# spear.net
KiCad netlist of a schematic drawn in EAGLE
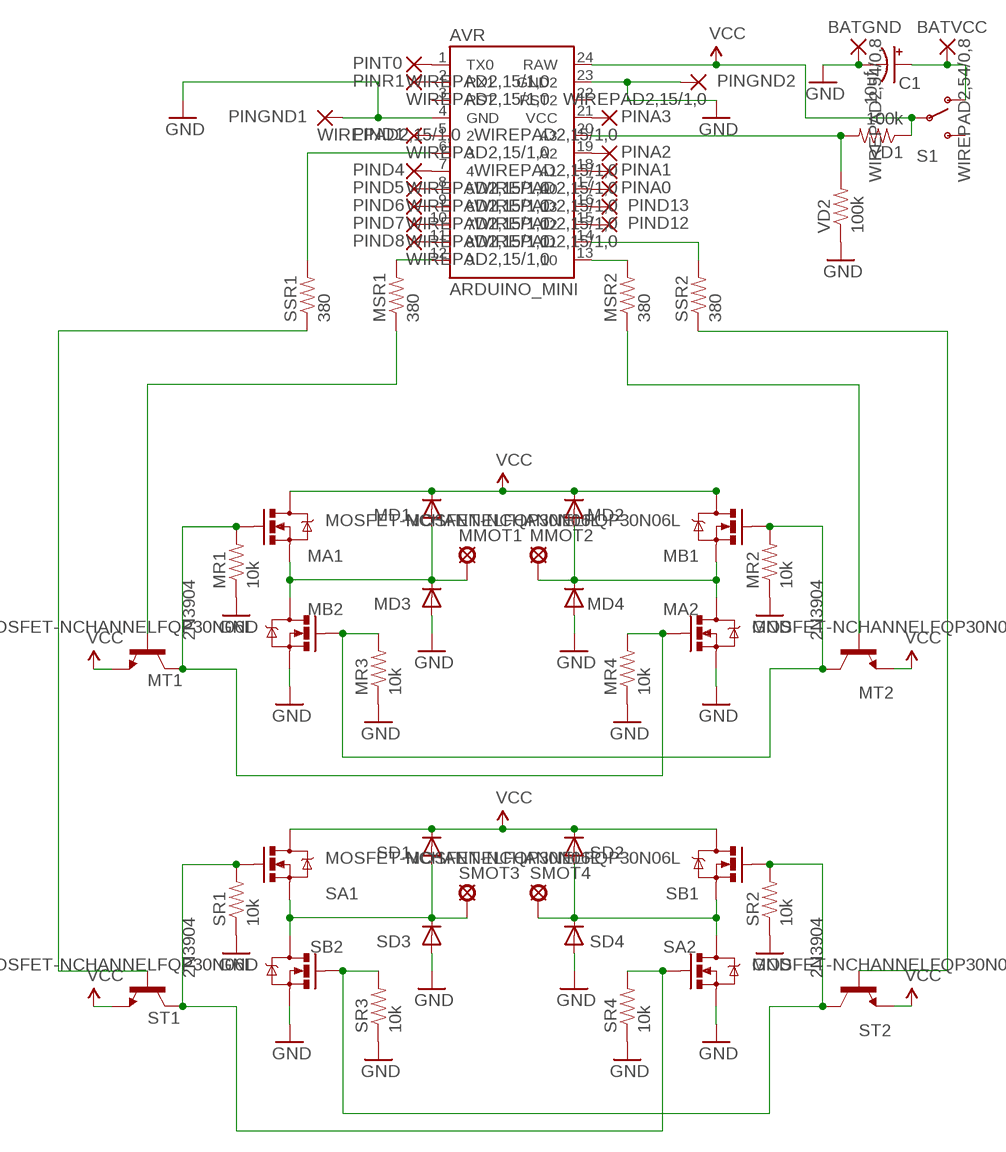
[diagram p0: schematic, sheet 1]

(export (version "E")
  (design (tool "Eeschema 10.0.6"))
  (components
    (comp (ref "AVR")
      (value "ARDUINO_MINI")
      (footprint "eagle-import:ARDUINO_MINI")
      (libsource (lib "eagle-import") (part "ARDUINO_MINI"))
    )
    (comp (ref "BATGND")
      (value "WIREPAD2,54/0,8")
      (footprint "eagle-import:2,54_0,8")
      (libsource (lib "eagle-import") (part "WIREPAD2,54/0,8"))
    )
    (comp (ref "BATVCC")
      (value "WIREPAD2,54/0,8")
      (footprint "eagle-import:2,54_0,8")
      (libsource (lib "eagle-import") (part "WIREPAD2,54/0,8"))
    )
    (comp (ref "C1")
      (value "10uf")
      (footprint "eagle-import:CPOL-RADIAL-10UF-25V")
      (libsource (lib "eagle-import") (part "CAP_POLPTH2"))
    )
    (comp (ref "MA1")
      (value "MOSFET-NCHANNELFQP30N06L")
      (footprint "eagle-import:TO220V")
      (libsource (lib "eagle-import") (part "MOSFET-NCHANNELFQP30N06L"))
    )
    (comp (ref "MA2")
      (value "MOSFET-NCHANNELFQP30N06L")
      (footprint "eagle-import:TO220V")
      (libsource (lib "eagle-import") (part "MOSFET-NCHANNELFQP30N06L"))
    )
    (comp (ref "MB1")
      (value "MOSFET-NCHANNELFQP30N06L")
      (footprint "eagle-import:TO220V")
      (libsource (lib "eagle-import") (part "MOSFET-NCHANNELFQP30N06L"))
    )
    (comp (ref "MB2")
      (value "MOSFET-NCHANNELFQP30N06L")
      (footprint "eagle-import:TO220V")
      (libsource (lib "eagle-import") (part "MOSFET-NCHANNELFQP30N06L"))
    )
    (comp (ref "MD1")
      (value "DIODEPTH")
      (footprint "eagle-import:DIODE-1N4001")
      (libsource (lib "eagle-import") (part "DIODEPTH"))
    )
    (comp (ref "MD2")
      (value "DIODEPTH")
      (footprint "eagle-import:DIODE-1N4001")
      (libsource (lib "eagle-import") (part "DIODEPTH"))
    )
    (comp (ref "MD3")
      (value "DIODEPTH")
      (footprint "eagle-import:DIODE-1N4001")
      (libsource (lib "eagle-import") (part "DIODEPTH"))
    )
    (comp (ref "MD4")
      (value "DIODEPTH")
      (footprint "eagle-import:DIODE-1N4001")
      (libsource (lib "eagle-import") (part "DIODEPTH"))
    )
    (comp (ref "MMOT1")
      (value "LSP13")
      (footprint "eagle-import:LSP13")
      (libsource (lib "eagle-import") (part "LSP13"))
    )
    (comp (ref "MMOT2")
      (value "LSP13")
      (footprint "eagle-import:LSP13")
      (libsource (lib "eagle-import") (part "LSP13"))
    )
    (comp (ref "MR1")
      (value "10k")
      (footprint "eagle-import:AXIAL-0.4")
      (libsource (lib "eagle-import") (part "RESISTORPTH-1/4W"))
    )
    (comp (ref "MR2")
      (value "10k")
      (footprint "eagle-import:AXIAL-0.4")
      (libsource (lib "eagle-import") (part "RESISTORPTH-1/4W"))
    )
    (comp (ref "MR3")
      (value "10k")
      (footprint "eagle-import:AXIAL-0.4")
      (libsource (lib "eagle-import") (part "RESISTORPTH-1/4W"))
    )
    (comp (ref "MR4")
      (value "10k")
      (footprint "eagle-import:AXIAL-0.4")
      (libsource (lib "eagle-import") (part "RESISTORPTH-1/4W"))
    )
    (comp (ref "MSR1")
      (value "380")
      (footprint "eagle-import:AXIAL-0.4")
      (libsource (lib "eagle-import") (part "RESISTORPTH-1/4W"))
    )
    (comp (ref "MSR2")
      (value "380")
      (footprint "eagle-import:AXIAL-0.4")
      (libsource (lib "eagle-import") (part "RESISTORPTH-1/4W"))
    )
    (comp (ref "MT1")
      (value "2N3904")
      (footprint "eagle-import:TO92")
      (libsource (lib "eagle-import") (part "2N3904"))
    )
    (comp (ref "MT2")
      (value "2N3904")
      (footprint "eagle-import:TO92")
      (libsource (lib "eagle-import") (part "2N3904"))
    )
    (comp (ref "PINA0")
      (value "WIREPAD2,15/1,0")
      (footprint "eagle-import:2,15_1,0")
      (libsource (lib "eagle-import") (part "WIREPAD2,15/1,0"))
    )
    (comp (ref "PINA1")
      (value "WIREPAD2,15/1,0")
      (footprint "eagle-import:2,15_1,0")
      (libsource (lib "eagle-import") (part "WIREPAD2,15/1,0"))
    )
    (comp (ref "PINA2")
      (value "WIREPAD2,15/1,0")
      (footprint "eagle-import:2,15_1,0")
      (libsource (lib "eagle-import") (part "WIREPAD2,15/1,0"))
    )
    (comp (ref "PINA3")
      (value "WIREPAD2,15/1,0")
      (footprint "eagle-import:2,15_1,0")
      (libsource (lib "eagle-import") (part "WIREPAD2,15/1,0"))
    )
    (comp (ref "PIND1")
      (value "WIREPAD2,15/1,0")
      (footprint "eagle-import:2,15_1,0")
      (libsource (lib "eagle-import") (part "WIREPAD2,15/1,0"))
    )
    (comp (ref "PIND4")
      (value "WIREPAD2,15/1,0")
      (footprint "eagle-import:2,15_1,0")
      (libsource (lib "eagle-import") (part "WIREPAD2,15/1,0"))
    )
    (comp (ref "PIND5")
      (value "WIREPAD2,15/1,0")
      (footprint "eagle-import:2,15_1,0")
      (libsource (lib "eagle-import") (part "WIREPAD2,15/1,0"))
    )
    (comp (ref "PIND6")
      (value "WIREPAD2,15/1,0")
      (footprint "eagle-import:2,15_1,0")
      (libsource (lib "eagle-import") (part "WIREPAD2,15/1,0"))
    )
    (comp (ref "PIND7")
      (value "WIREPAD2,15/1,0")
      (footprint "eagle-import:2,15_1,0")
      (libsource (lib "eagle-import") (part "WIREPAD2,15/1,0"))
    )
    (comp (ref "PIND8")
      (value "WIREPAD2,15/1,0")
      (footprint "eagle-import:2,15_1,0")
      (libsource (lib "eagle-import") (part "WIREPAD2,15/1,0"))
    )
    (comp (ref "PIND12")
      (value "WIREPAD2,15/1,0")
      (footprint "eagle-import:2,15_1,0")
      (libsource (lib "eagle-import") (part "WIREPAD2,15/1,0"))
    )
    (comp (ref "PIND13")
      (value "WIREPAD2,15/1,0")
      (footprint "eagle-import:2,15_1,0")
      (libsource (lib "eagle-import") (part "WIREPAD2,15/1,0"))
    )
    (comp (ref "PINGND1")
      (value "WIREPAD2,15/1,0")
      (footprint "eagle-import:2,15_1,0")
      (libsource (lib "eagle-import") (part "WIREPAD2,15/1,0"))
    )
    (comp (ref "PINGND2")
      (value "WIREPAD2,15/1,0")
      (footprint "eagle-import:2,15_1,0")
      (libsource (lib "eagle-import") (part "WIREPAD2,15/1,0"))
    )
    (comp (ref "PINR1")
      (value "WIREPAD2,15/1,0")
      (footprint "eagle-import:2,15_1,0")
      (libsource (lib "eagle-import") (part "WIREPAD2,15/1,0"))
    )
    (comp (ref "PINT0")
      (value "WIREPAD2,15/1,0")
      (footprint "eagle-import:2,15_1,0")
      (libsource (lib "eagle-import") (part "WIREPAD2,15/1,0"))
    )
    (comp (ref "S1")
      (value "SWITCH-SPSTPTH")
      (footprint "eagle-import:SWITCH-SPDT")
      (libsource (lib "eagle-import") (part "SWITCH-SPSTPTH"))
    )
    (comp (ref "SA1")
      (value "MOSFET-NCHANNELFQP30N06L")
      (footprint "eagle-import:TO220V")
      (libsource (lib "eagle-import") (part "MOSFET-NCHANNELFQP30N06L"))
    )
    (comp (ref "SA2")
      (value "MOSFET-NCHANNELFQP30N06L")
      (footprint "eagle-import:TO220V")
      (libsource (lib "eagle-import") (part "MOSFET-NCHANNELFQP30N06L"))
    )
    (comp (ref "SB1")
      (value "MOSFET-NCHANNELFQP30N06L")
      (footprint "eagle-import:TO220V")
      (libsource (lib "eagle-import") (part "MOSFET-NCHANNELFQP30N06L"))
    )
    (comp (ref "SB2")
      (value "MOSFET-NCHANNELFQP30N06L")
      (footprint "eagle-import:TO220V")
      (libsource (lib "eagle-import") (part "MOSFET-NCHANNELFQP30N06L"))
    )
    (comp (ref "SD1")
      (value "DIODEPTH")
      (footprint "eagle-import:DIODE-1N4001")
      (libsource (lib "eagle-import") (part "DIODEPTH"))
    )
    (comp (ref "SD2")
      (value "DIODEPTH")
      (footprint "eagle-import:DIODE-1N4001")
      (libsource (lib "eagle-import") (part "DIODEPTH"))
    )
    (comp (ref "SD3")
      (value "DIODEPTH")
      (footprint "eagle-import:DIODE-1N4001")
      (libsource (lib "eagle-import") (part "DIODEPTH"))
    )
    (comp (ref "SD4")
      (value "DIODEPTH")
      (footprint "eagle-import:DIODE-1N4001")
      (libsource (lib "eagle-import") (part "DIODEPTH"))
    )
    (comp (ref "SMOT3")
      (value "LSP13")
      (footprint "eagle-import:LSP13")
      (libsource (lib "eagle-import") (part "LSP13"))
    )
    (comp (ref "SMOT4")
      (value "LSP13")
      (footprint "eagle-import:LSP13")
      (libsource (lib "eagle-import") (part "LSP13"))
    )
    (comp (ref "SR1")
      (value "10k")
      (footprint "eagle-import:AXIAL-0.4")
      (libsource (lib "eagle-import") (part "RESISTORPTH-1/4W"))
    )
    (comp (ref "SR2")
      (value "10k")
      (footprint "eagle-import:AXIAL-0.4")
      (libsource (lib "eagle-import") (part "RESISTORPTH-1/4W"))
    )
    (comp (ref "SR3")
      (value "10k")
      (footprint "eagle-import:AXIAL-0.4")
      (libsource (lib "eagle-import") (part "RESISTORPTH-1/4W"))
    )
    (comp (ref "SR4")
      (value "10k")
      (footprint "eagle-import:AXIAL-0.4")
      (libsource (lib "eagle-import") (part "RESISTORPTH-1/4W"))
    )
    (comp (ref "SSR1")
      (value "380")
      (footprint "eagle-import:AXIAL-0.4")
      (libsource (lib "eagle-import") (part "RESISTORPTH-1/4W"))
    )
    (comp (ref "SSR2")
      (value "380")
      (footprint "eagle-import:AXIAL-0.4")
      (libsource (lib "eagle-import") (part "RESISTORPTH-1/4W"))
    )
    (comp (ref "ST1")
      (value "2N3904")
      (footprint "eagle-import:TO92")
      (libsource (lib "eagle-import") (part "2N3904"))
    )
    (comp (ref "ST2")
      (value "2N3904")
      (footprint "eagle-import:TO92")
      (libsource (lib "eagle-import") (part "2N3904"))
    )
    (comp (ref "VD1")
      (value "100k")
      (footprint "eagle-import:AXIAL-0.4")
      (libsource (lib "eagle-import") (part "RESISTORPTH-1/4W"))
    )
    (comp (ref "VD2")
      (value "100k")
      (footprint "eagle-import:AXIAL-0.4")
      (libsource (lib "eagle-import") (part "RESISTORPTH-1/4W"))
    )
  )
  (nets
    (net (code "1") (name "GND") (class "Default")
      (node (ref "AVR") (pin "23") (pinfunction "GND2_23") (pintype "bidirectional"))
      (node (ref "AVR") (pin "4") (pinfunction "GND_4") (pintype "bidirectional"))
      (node (ref "BATGND") (pin "1") (pinfunction "P_1") (pintype "passive"))
      (node (ref "C1") (pin "2") (pinfunction "-_2") (pintype "passive"))
      (node (ref "MA2") (pin "3") (pinfunction "S_3") (pintype "passive"))
      (node (ref "MB2") (pin "3") (pinfunction "S_3") (pintype "passive"))
      (node (ref "MD3") (pin "A") (pinfunction "A_A") (pintype "passive"))
      (node (ref "MD4") (pin "A") (pinfunction "A_A") (pintype "passive"))
      (node (ref "MR1") (pin "P$1") (pinfunction "1_P$1") (pintype "passive"))
      (node (ref "MR2") (pin "P$1") (pinfunction "1_P$1") (pintype "passive"))
      (node (ref "MR3") (pin "P$1") (pinfunction "1_P$1") (pintype "passive"))
      (node (ref "MR4") (pin "P$1") (pinfunction "1_P$1") (pintype "passive"))
      (node (ref "PINGND1") (pin "1") (pinfunction "P_1") (pintype "passive"))
      (node (ref "PINGND2") (pin "1") (pinfunction "P_1") (pintype "passive"))
      (node (ref "SA2") (pin "3") (pinfunction "S_3") (pintype "passive"))
      (node (ref "SB2") (pin "3") (pinfunction "S_3") (pintype "passive"))
      (node (ref "SD3") (pin "A") (pinfunction "A_A") (pintype "passive"))
      (node (ref "SD4") (pin "A") (pinfunction "A_A") (pintype "passive"))
      (node (ref "SR1") (pin "P$1") (pinfunction "1_P$1") (pintype "passive"))
      (node (ref "SR2") (pin "P$1") (pinfunction "1_P$1") (pintype "passive"))
      (node (ref "SR3") (pin "P$1") (pinfunction "1_P$1") (pintype "passive"))
      (node (ref "SR4") (pin "P$1") (pinfunction "1_P$1") (pintype "passive"))
      (node (ref "VD2") (pin "P$1") (pinfunction "1_P$1") (pintype "passive"))
    )
    (net (code "2") (name "Net-(AVR-2)") (class "Default")
      (node (ref "AVR") (pin "5") (pinfunction "2_5") (pintype "bidirectional"))
      (node (ref "PIND1") (pin "1") (pinfunction "P_1") (pintype "passive"))
    )
    (net (code "3") (name "Net-(AVR-3)") (class "Default")
      (node (ref "AVR") (pin "6") (pinfunction "3_6") (pintype "bidirectional"))
      (node (ref "SSR1") (pin "P$2") (pinfunction "2_P$2") (pintype "passive"))
    )
    (net (code "4") (name "Net-(AVR-4)") (class "Default")
      (node (ref "AVR") (pin "7") (pinfunction "4_7") (pintype "bidirectional"))
      (node (ref "PIND4") (pin "1") (pinfunction "P_1") (pintype "passive"))
    )
    (net (code "5") (name "Net-(AVR-5)") (class "Default")
      (node (ref "AVR") (pin "8") (pinfunction "5_8") (pintype "bidirectional"))
      (node (ref "PIND5") (pin "1") (pinfunction "P_1") (pintype "passive"))
    )
    (net (code "6") (name "Net-(AVR-6)") (class "Default")
      (node (ref "AVR") (pin "9") (pinfunction "6_9") (pintype "bidirectional"))
      (node (ref "PIND6") (pin "1") (pinfunction "P_1") (pintype "passive"))
    )
    (net (code "7") (name "Net-(AVR-7)") (class "Default")
      (node (ref "AVR") (pin "10") (pinfunction "7_10") (pintype "bidirectional"))
      (node (ref "PIND7") (pin "1") (pinfunction "P_1") (pintype "passive"))
    )
    (net (code "8") (name "Net-(AVR-8)") (class "Default")
      (node (ref "AVR") (pin "11") (pinfunction "8_11") (pintype "bidirectional"))
      (node (ref "PIND8") (pin "1") (pinfunction "P_1") (pintype "passive"))
    )
    (net (code "9") (name "Net-(AVR-9)") (class "Default")
      (node (ref "AVR") (pin "12") (pinfunction "9_12") (pintype "bidirectional"))
      (node (ref "MSR1") (pin "P$2") (pinfunction "2_P$2") (pintype "passive"))
    )
    (net (code "10") (name "Net-(AVR-10)") (class "Default")
      (node (ref "AVR") (pin "13") (pinfunction "10_13") (pintype "bidirectional"))
      (node (ref "MSR2") (pin "P$2") (pinfunction "2_P$2") (pintype "passive"))
    )
    (net (code "11") (name "Net-(AVR-11)") (class "Default")
      (node (ref "AVR") (pin "14") (pinfunction "11_14") (pintype "bidirectional"))
      (node (ref "SSR2") (pin "P$2") (pinfunction "2_P$2") (pintype "passive"))
    )
    (net (code "12") (name "Net-(AVR-12)") (class "Default")
      (node (ref "AVR") (pin "15") (pinfunction "12_15") (pintype "bidirectional"))
      (node (ref "PIND12") (pin "1") (pinfunction "P_1") (pintype "passive"))
    )
    (net (code "13") (name "Net-(AVR-13)") (class "Default")
      (node (ref "AVR") (pin "16") (pinfunction "13_16") (pintype "bidirectional"))
      (node (ref "PIND13") (pin "1") (pinfunction "P_1") (pintype "passive"))
    )
    (net (code "14") (name "Net-(AVR-A0)") (class "Default")
      (node (ref "AVR") (pin "17") (pinfunction "A0_17") (pintype "bidirectional"))
      (node (ref "PINA0") (pin "1") (pinfunction "P_1") (pintype "passive"))
    )
    (net (code "15") (name "Net-(AVR-A1)") (class "Default")
      (node (ref "AVR") (pin "18") (pinfunction "A1_18") (pintype "bidirectional"))
      (node (ref "PINA1") (pin "1") (pinfunction "P_1") (pintype "passive"))
    )
    (net (code "16") (name "Net-(AVR-A2)") (class "Default")
      (node (ref "AVR") (pin "19") (pinfunction "A2_19") (pintype "bidirectional"))
      (node (ref "PINA2") (pin "1") (pinfunction "P_1") (pintype "passive"))
    )
    (net (code "17") (name "Net-(AVR-A3)") (class "Default")
      (node (ref "AVR") (pin "20") (pinfunction "A3_20") (pintype "bidirectional"))
      (node (ref "VD1") (pin "P$2") (pinfunction "2_P$2") (pintype "passive"))
      (node (ref "VD2") (pin "P$2") (pinfunction "2_P$2") (pintype "passive"))
    )
    (net (code "18") (name "Net-(AVR-RX1)") (class "Default")
      (node (ref "AVR") (pin "2") (pinfunction "RX1_2") (pintype "bidirectional"))
      (node (ref "PINR1") (pin "1") (pinfunction "P_1") (pintype "passive"))
    )
    (net (code "19") (name "Net-(AVR-TX0)") (class "Default")
      (node (ref "AVR") (pin "1") (pinfunction "TX0_1") (pintype "bidirectional"))
      (node (ref "PINT0") (pin "1") (pinfunction "P_1") (pintype "passive"))
    )
    (net (code "20") (name "Net-(AVR-VCC)") (class "Default")
      (node (ref "AVR") (pin "21") (pinfunction "VCC_21") (pintype "bidirectional"))
      (node (ref "PINA3") (pin "1") (pinfunction "P_1") (pintype "passive"))
    )
    (net (code "21") (name "Net-(BATVCC-P)") (class "Default")
      (node (ref "BATVCC") (pin "1") (pinfunction "P_1") (pintype "passive"))
      (node (ref "C1") (pin "1") (pinfunction "+_1") (pintype "passive"))
      (node (ref "S1") (pin "1") (pinfunction "O_1") (pintype "passive"))
    )
    (net (code "22") (name "Net-(MA1-G)") (class "Default")
      (node (ref "MA1") (pin "1") (pinfunction "G_1") (pintype "passive"))
      (node (ref "MA2") (pin "1") (pinfunction "G_1") (pintype "passive"))
      (node (ref "MR1") (pin "P$2") (pinfunction "2_P$2") (pintype "passive"))
      (node (ref "MR4") (pin "P$2") (pinfunction "2_P$2") (pintype "passive"))
      (node (ref "MT1") (pin "1") (pinfunction "C_1") (pintype "passive"))
    )
    (net (code "23") (name "Net-(MA1-S)") (class "Default")
      (node (ref "MA1") (pin "3") (pinfunction "S_3") (pintype "passive"))
      (node (ref "MB2") (pin "2") (pinfunction "D_2") (pintype "passive"))
      (node (ref "MD1") (pin "A") (pinfunction "A_A") (pintype "passive"))
      (node (ref "MD3") (pin "C") (pinfunction "C_C") (pintype "passive"))
      (node (ref "MMOT1") (pin "MP") (pinfunction "MP_MP") (pintype "passive"))
    )
    (net (code "24") (name "Net-(MA2-D)") (class "Default")
      (node (ref "MA2") (pin "2") (pinfunction "D_2") (pintype "passive"))
      (node (ref "MB1") (pin "3") (pinfunction "S_3") (pintype "passive"))
      (node (ref "MD2") (pin "A") (pinfunction "A_A") (pintype "passive"))
      (node (ref "MD4") (pin "C") (pinfunction "C_C") (pintype "passive"))
      (node (ref "MMOT2") (pin "MP") (pinfunction "MP_MP") (pintype "passive"))
    )
    (net (code "25") (name "Net-(MB1-G)") (class "Default")
      (node (ref "MB1") (pin "1") (pinfunction "G_1") (pintype "passive"))
      (node (ref "MB2") (pin "1") (pinfunction "G_1") (pintype "passive"))
      (node (ref "MR2") (pin "P$2") (pinfunction "2_P$2") (pintype "passive"))
      (node (ref "MR3") (pin "P$2") (pinfunction "2_P$2") (pintype "passive"))
      (node (ref "MT2") (pin "1") (pinfunction "C_1") (pintype "passive"))
    )
    (net (code "26") (name "Net-(MSR1-1)") (class "Default")
      (node (ref "MSR1") (pin "P$1") (pinfunction "1_P$1") (pintype "passive"))
      (node (ref "MT1") (pin "2") (pinfunction "B_2") (pintype "passive"))
    )
    (net (code "27") (name "Net-(MSR2-1)") (class "Default")
      (node (ref "MSR2") (pin "P$1") (pinfunction "1_P$1") (pintype "passive"))
      (node (ref "MT2") (pin "2") (pinfunction "B_2") (pintype "passive"))
    )
    (net (code "28") (name "Net-(SA1-G)") (class "Default")
      (node (ref "SA1") (pin "1") (pinfunction "G_1") (pintype "passive"))
      (node (ref "SA2") (pin "1") (pinfunction "G_1") (pintype "passive"))
      (node (ref "SR1") (pin "P$2") (pinfunction "2_P$2") (pintype "passive"))
      (node (ref "SR4") (pin "P$2") (pinfunction "2_P$2") (pintype "passive"))
      (node (ref "ST1") (pin "1") (pinfunction "C_1") (pintype "passive"))
    )
    (net (code "29") (name "Net-(SA1-S)") (class "Default")
      (node (ref "SA1") (pin "3") (pinfunction "S_3") (pintype "passive"))
      (node (ref "SB2") (pin "2") (pinfunction "D_2") (pintype "passive"))
      (node (ref "SD1") (pin "A") (pinfunction "A_A") (pintype "passive"))
      (node (ref "SD3") (pin "C") (pinfunction "C_C") (pintype "passive"))
      (node (ref "SMOT3") (pin "MP") (pinfunction "MP_MP") (pintype "passive"))
    )
    (net (code "30") (name "Net-(SA2-D)") (class "Default")
      (node (ref "SA2") (pin "2") (pinfunction "D_2") (pintype "passive"))
      (node (ref "SB1") (pin "3") (pinfunction "S_3") (pintype "passive"))
      (node (ref "SD2") (pin "A") (pinfunction "A_A") (pintype "passive"))
      (node (ref "SD4") (pin "C") (pinfunction "C_C") (pintype "passive"))
      (node (ref "SMOT4") (pin "MP") (pinfunction "MP_MP") (pintype "passive"))
    )
    (net (code "31") (name "Net-(SB1-G)") (class "Default")
      (node (ref "SB1") (pin "1") (pinfunction "G_1") (pintype "passive"))
      (node (ref "SB2") (pin "1") (pinfunction "G_1") (pintype "passive"))
      (node (ref "SR2") (pin "P$2") (pinfunction "2_P$2") (pintype "passive"))
      (node (ref "SR3") (pin "P$2") (pinfunction "2_P$2") (pintype "passive"))
      (node (ref "ST2") (pin "1") (pinfunction "C_1") (pintype "passive"))
    )
    (net (code "32") (name "Net-(SSR1-1)") (class "Default")
      (node (ref "SSR1") (pin "P$1") (pinfunction "1_P$1") (pintype "passive"))
      (node (ref "ST1") (pin "2") (pinfunction "B_2") (pintype "passive"))
    )
    (net (code "33") (name "Net-(SSR2-1)") (class "Default")
      (node (ref "SSR2") (pin "P$1") (pinfunction "1_P$1") (pintype "passive"))
      (node (ref "ST2") (pin "2") (pinfunction "B_2") (pintype "passive"))
    )
    (net (code "34") (name "VCC") (class "Default")
      (node (ref "AVR") (pin "24") (pinfunction "RAW_24") (pintype "bidirectional"))
      (node (ref "MA1") (pin "2") (pinfunction "D_2") (pintype "passive"))
      (node (ref "MB1") (pin "2") (pinfunction "D_2") (pintype "passive"))
      (node (ref "MD1") (pin "C") (pinfunction "C_C") (pintype "passive"))
      (node (ref "MD2") (pin "C") (pinfunction "C_C") (pintype "passive"))
      (node (ref "MT1") (pin "3") (pinfunction "E_3") (pintype "passive"))
      (node (ref "MT2") (pin "3") (pinfunction "E_3") (pintype "passive"))
      (node (ref "S1") (pin "2") (pinfunction "P_2") (pintype "passive"))
      (node (ref "SA1") (pin "2") (pinfunction "D_2") (pintype "passive"))
      (node (ref "SB1") (pin "2") (pinfunction "D_2") (pintype "passive"))
      (node (ref "SD1") (pin "C") (pinfunction "C_C") (pintype "passive"))
      (node (ref "SD2") (pin "C") (pinfunction "C_C") (pintype "passive"))
      (node (ref "ST1") (pin "3") (pinfunction "E_3") (pintype "passive"))
      (node (ref "ST2") (pin "3") (pinfunction "E_3") (pintype "passive"))
      (node (ref "VD1") (pin "P$1") (pinfunction "1_P$1") (pintype "passive"))
    )
    (net (code "35") (name "unconnected-(AVR-RST-Pad3)") (class "Default")
      (node (ref "AVR") (pin "3") (pinfunction "RST_3") (pintype "bidirectional"))
    )
    (net (code "36") (name "unconnected-(AVR-RST2-Pad22)") (class "Default")
      (node (ref "AVR") (pin "22") (pinfunction "RST2_22") (pintype "bidirectional"))
    )
    (net (code "37") (name "unconnected-(S1-S-Pad3)") (class "Default")
      (node (ref "S1") (pin "3") (pinfunction "S_3") (pintype "passive"))
    )
  )
)
